# W01.net
KiCad netlist of a schematic drawn in EAGLE
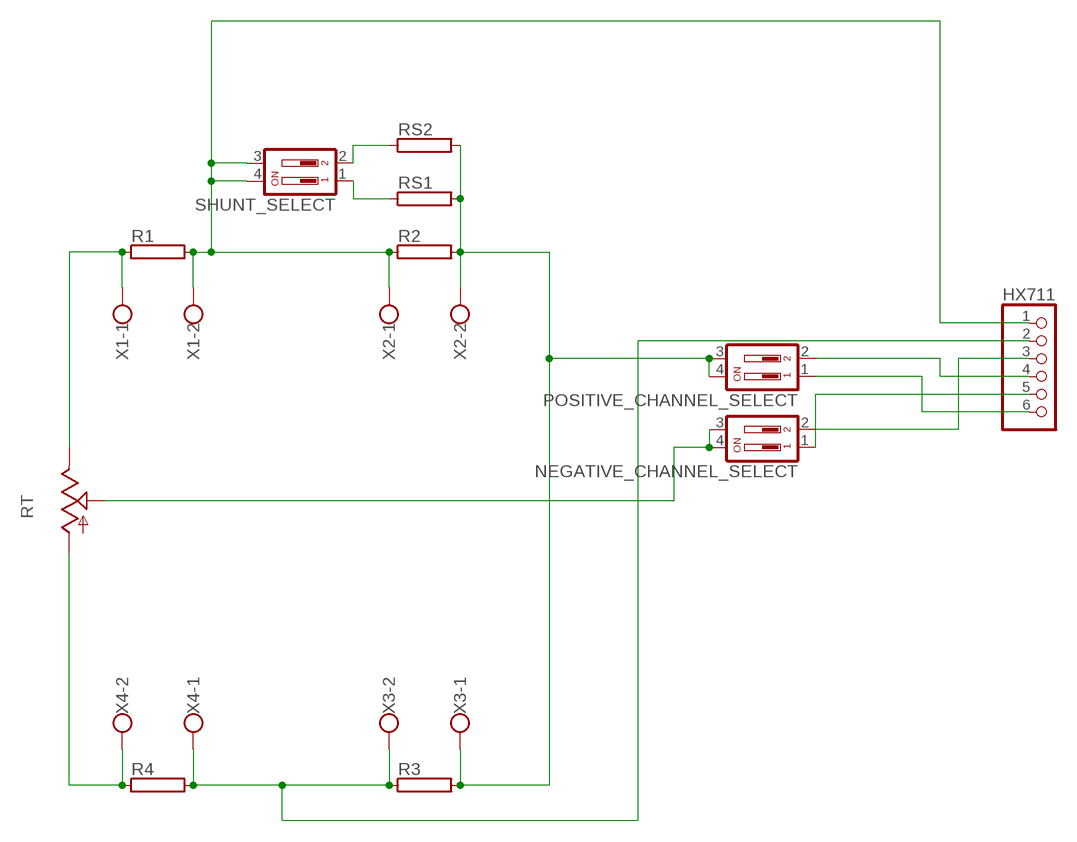
[diagram p0: schematic, sheet 1]

(export (version "E")
  (design (tool "Eeschema 10.0.6"))
  (components
    (comp (ref "HX711")
      (value "PINHD-1X6")
      (footprint "eagle-import:1X06")
      (libsource (lib "eagle-import") (part "PINHD-1X6"))
    )
    (comp (ref "NEGATIVE_CHANNEL_SELECT")
      (value "DIP02YL")
      (footprint "eagle-import:DIP02YL")
      (libsource (lib "eagle-import") (part "DIP02YL"))
    )
    (comp (ref "POSITIVE_CHANNEL_SELECT")
      (value "DIP02YL")
      (footprint "eagle-import:DIP02YL")
      (libsource (lib "eagle-import") (part "DIP02YL"))
    )
    (comp (ref "R1")
      (value "RAC03")
      (footprint "eagle-import:AC03")
      (libsource (lib "eagle-import") (part "RAC03"))
    )
    (comp (ref "R2")
      (value "RAC03")
      (footprint "eagle-import:AC03")
      (libsource (lib "eagle-import") (part "RAC03"))
    )
    (comp (ref "R3")
      (value "RAC03")
      (footprint "eagle-import:AC03")
      (libsource (lib "eagle-import") (part "RAC03"))
    )
    (comp (ref "R4")
      (value "RAC03")
      (footprint "eagle-import:AC03")
      (libsource (lib "eagle-import") (part "RAC03"))
    )
    (comp (ref "RS1")
      (value "RAC03")
      (footprint "eagle-import:AC03")
      (libsource (lib "eagle-import") (part "RAC03"))
    )
    (comp (ref "RS2")
      (value "RAC03")
      (footprint "eagle-import:AC03")
      (libsource (lib "eagle-import") (part "RAC03"))
    )
    (comp (ref "RT")
      (value "TRIM_US-RJ9W")
      (footprint "eagle-import:RJ9W")
      (libsource (lib "eagle-import") (part "TRIM_US-RJ9W"))
    )
    (comp (ref "SHUNT_SELECT")
      (value "DIP02YL")
      (footprint "eagle-import:DIP02YL")
      (libsource (lib "eagle-import") (part "DIP02YL"))
    )
    (comp (ref "X1")
      (value "W237-102")
      (footprint "eagle-import:W237-102")
      (fields (field (name "MPN") "237-102"))
      (libsource (lib "eagle-import") (part "W237-102"))
    )
    (comp (ref "X2")
      (value "W237-102")
      (footprint "eagle-import:W237-102")
      (fields (field (name "MPN") "237-102"))
      (libsource (lib "eagle-import") (part "W237-102"))
    )
    (comp (ref "X3")
      (value "W237-102")
      (footprint "eagle-import:W237-102")
      (fields (field (name "MPN") "237-102"))
      (libsource (lib "eagle-import") (part "W237-102"))
    )
    (comp (ref "X4")
      (value "W237-102")
      (footprint "eagle-import:W237-102")
      (fields (field (name "MPN") "237-102"))
      (libsource (lib "eagle-import") (part "W237-102"))
    )
  )
  (nets
    (net (code "1") (name "Net-(HX711-Pad3)") (class "Default")
      (node (ref "HX711") (pin "3") (pinfunction "3_3") (pintype "passive"))
      (node (ref "NEGATIVE_CHANNEL_SELECT") (pin "2") (pinfunction "2_2") (pintype "passive"))
    )
    (net (code "2") (name "Net-(HX711-Pad4)") (class "Default")
      (node (ref "HX711") (pin "4") (pinfunction "4_4") (pintype "passive"))
      (node (ref "POSITIVE_CHANNEL_SELECT") (pin "2") (pinfunction "2_2") (pintype "passive"))
    )
    (net (code "3") (name "Net-(HX711-Pad5)") (class "Default")
      (node (ref "HX711") (pin "5") (pinfunction "5_5") (pintype "passive"))
      (node (ref "NEGATIVE_CHANNEL_SELECT") (pin "1") (pinfunction "1_1") (pintype "passive"))
    )
    (net (code "4") (name "Net-(HX711-Pad6)") (class "Default")
      (node (ref "HX711") (pin "6") (pinfunction "6_6") (pintype "passive"))
      (node (ref "POSITIVE_CHANNEL_SELECT") (pin "1") (pinfunction "1_1") (pintype "passive"))
    )
    (net (code "5") (name "Net-(NEGATIVE_CHANNEL_SELECT-Pad3)") (class "Default")
      (node (ref "NEGATIVE_CHANNEL_SELECT") (pin "3") (pinfunction "3_3") (pintype "passive"))
      (node (ref "NEGATIVE_CHANNEL_SELECT") (pin "4") (pinfunction "4_4") (pintype "passive"))
      (node (ref "RT") (pin "S") (pinfunction "S_S") (pintype "passive"))
    )
    (net (code "6") (name "Net-(RS1-Pad1)") (class "Default")
      (node (ref "RS1") (pin "1") (pinfunction "1_1") (pintype "passive"))
      (node (ref "SHUNT_SELECT") (pin "1") (pinfunction "1_1") (pintype "passive"))
    )
    (net (code "7") (name "Net-(RS2-Pad1)") (class "Default")
      (node (ref "RS2") (pin "1") (pinfunction "1_1") (pintype "passive"))
      (node (ref "SHUNT_SELECT") (pin "2") (pinfunction "2_2") (pintype "passive"))
    )
    (net (code "8") (name "Net-(X1A-KL)") (class "Default")
      (node (ref "R1") (pin "1") (pinfunction "1_1") (pintype "passive"))
      (node (ref "RT") (pin "E") (pinfunction "E_E") (pintype "passive"))
      (node (ref "X1") (pin "1") (pinfunction "KL_1") (pintype "passive"))
    )
    (net (code "9") (name "Net-(X1B-KL)") (class "Default")
      (node (ref "HX711") (pin "1") (pinfunction "1_1") (pintype "passive"))
      (node (ref "R1") (pin "2") (pinfunction "2_2") (pintype "passive"))
      (node (ref "R2") (pin "1") (pinfunction "1_1") (pintype "passive"))
      (node (ref "SHUNT_SELECT") (pin "3") (pinfunction "3_3") (pintype "passive"))
      (node (ref "SHUNT_SELECT") (pin "4") (pinfunction "4_4") (pintype "passive"))
      (node (ref "X1") (pin "2") (pinfunction "KL_2") (pintype "passive"))
      (node (ref "X2") (pin "1") (pinfunction "KL_1") (pintype "passive"))
    )
    (net (code "10") (name "Net-(X2B-KL)") (class "Default")
      (node (ref "POSITIVE_CHANNEL_SELECT") (pin "3") (pinfunction "3_3") (pintype "passive"))
      (node (ref "POSITIVE_CHANNEL_SELECT") (pin "4") (pinfunction "4_4") (pintype "passive"))
      (node (ref "R2") (pin "2") (pinfunction "2_2") (pintype "passive"))
      (node (ref "R3") (pin "2") (pinfunction "2_2") (pintype "passive"))
      (node (ref "RS1") (pin "2") (pinfunction "2_2") (pintype "passive"))
      (node (ref "RS2") (pin "2") (pinfunction "2_2") (pintype "passive"))
      (node (ref "X2") (pin "2") (pinfunction "KL_2") (pintype "passive"))
      (node (ref "X3") (pin "1") (pinfunction "KL_1") (pintype "passive"))
    )
    (net (code "11") (name "Net-(X3B-KL)") (class "Default")
      (node (ref "HX711") (pin "2") (pinfunction "2_2") (pintype "passive"))
      (node (ref "R3") (pin "1") (pinfunction "1_1") (pintype "passive"))
      (node (ref "R4") (pin "2") (pinfunction "2_2") (pintype "passive"))
      (node (ref "X3") (pin "2") (pinfunction "KL_2") (pintype "passive"))
      (node (ref "X4") (pin "1") (pinfunction "KL_1") (pintype "passive"))
    )
    (net (code "12") (name "Net-(X4B-KL)") (class "Default")
      (node (ref "R4") (pin "1") (pinfunction "1_1") (pintype "passive"))
      (node (ref "RT") (pin "A") (pinfunction "A_A") (pintype "passive"))
      (node (ref "X4") (pin "2") (pinfunction "KL_2") (pintype "passive"))
    )
  )
)
